# DDR.net
KiCad netlist of a schematic drawn in Altium Designer
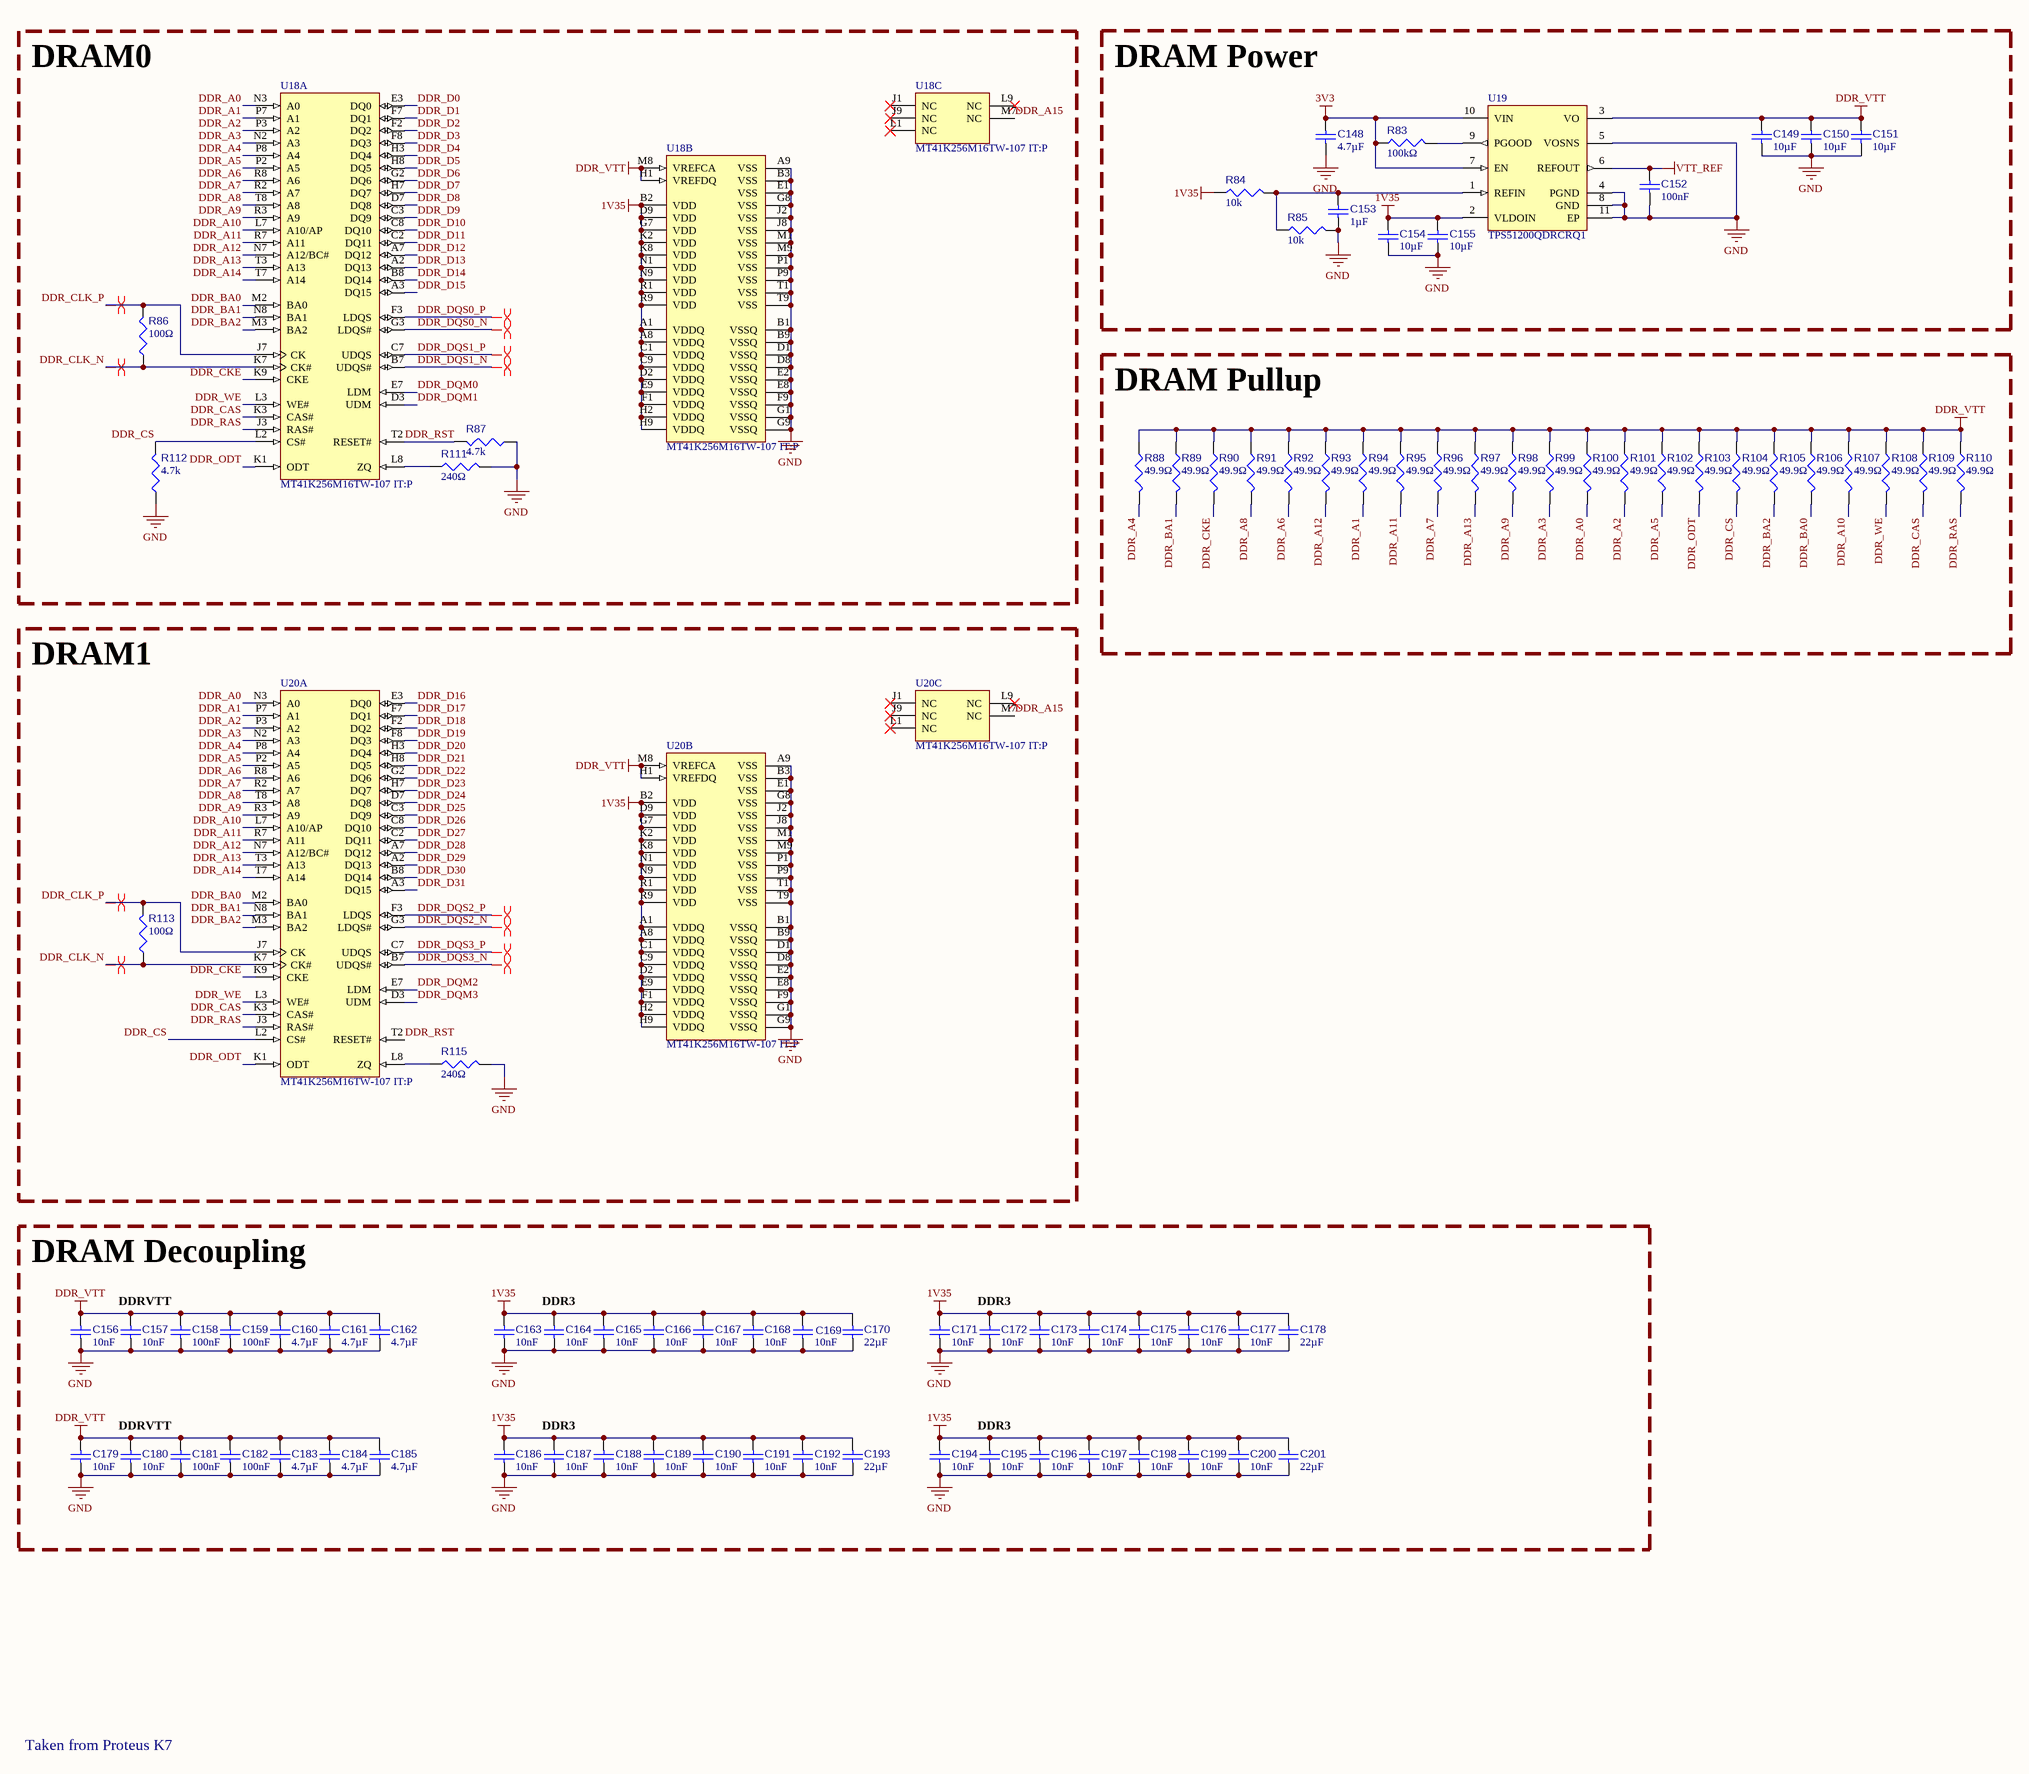
[diagram p0: DDR.SchDoc]

(export (version "E")
  (design (tool "Eeschema 10.0.6"))
  (components
    (comp (ref "C148")
      (value "4.7µF")
      (footprint "CAP-0402-MFG")
      (description "0402-4.7u-20%-25V-X5R")
      (fields (field (name "TOLERANCE") "20%") (field (name "MANUFACTURER PART NUMBER") "GRM155R61E475ME15D"))
      (libsource (lib "UC Berkeley – EE194") (part "CAP-NP-2P"))
    )
    (comp (ref "C149")
      (value "10µF")
      (footprint "CAP-0603-MFG")
      (description "0603-10u-10%-16V-X5R-AECQ200")
      (fields (field (name "TOLERANCE") "10%") (field (name "MANUFACTURER PART NUMBER") "GRT188R61C106KE13J"))
      (libsource (lib "UC Berkeley – EE194") (part "CAP-NP-2P"))
    )
    (comp (ref "C150")
      (value "10µF")
      (footprint "CAP-0603-MFG")
      (description "0603-10u-10%-16V-X5R-AECQ200")
      (fields (field (name "TOLERANCE") "10%") (field (name "MANUFACTURER PART NUMBER") "GRT188R61C106KE13J"))
      (libsource (lib "UC Berkeley – EE194") (part "CAP-NP-2P"))
    )
    (comp (ref "C151")
      (value "10µF")
      (footprint "CAP-0603-MFG")
      (description "0603-10u-10%-16V-X5R-AECQ200")
      (fields (field (name "TOLERANCE") "10%") (field (name "MANUFACTURER PART NUMBER") "GRT188R61C106KE13J"))
      (libsource (lib "UC Berkeley – EE194") (part "CAP-NP-2P"))
    )
    (comp (ref "C152")
      (value "100nF")
      (footprint "CAP-0402-MFG")
      (description "0402-100n-10%-16V-X7R-AECQ200")
      (fields (field (name "TOLERANCE") "10%") (field (name "MANUFACTURER PART NUMBER") "CL05B104KO5VPNC"))
      (libsource (lib "UC Berkeley – EE194") (part "CAP-NP-2P"))
    )
    (comp (ref "C153")
      (value "1µF")
      (footprint "CAP-0402-MFG")
      (description "0402-1u-10%-16V-X6S-AECQ200")
      (fields (field (name "MANUFACTURER PART NUMBER") "GRT155C81C105KE13J") (field (name "TOLERANCE") "10%"))
      (libsource (lib "UC Berkeley – EE194") (part "CAP-NP-2P"))
    )
    (comp (ref "C154")
      (value "10µF")
      (footprint "CAP-0603-MFG")
      (description "0603-10u-10%-16V-X5R-AECQ200")
      (fields (field (name "TOLERANCE") "10%") (field (name "MANUFACTURER PART NUMBER") "GRT188R61C106KE13J"))
      (libsource (lib "UC Berkeley – EE194") (part "CAP-NP-2P"))
    )
    (comp (ref "C155")
      (value "10µF")
      (footprint "CAP-0603-MFG")
      (description "0603-10u-10%-16V-X5R-AECQ200")
      (fields (field (name "TOLERANCE") "10%") (field (name "MANUFACTURER PART NUMBER") "GRT188R61C106KE13J"))
      (libsource (lib "UC Berkeley – EE194") (part "CAP-NP-2P"))
    )
    (comp (ref "C156")
      (value "10nF")
      (footprint "CAP-0402-MFG")
      (description "0402-10n-10%-16V-X7R-AECQ200")
      (fields (field (name "MANUFACTURER PART NUMBER") "AC0402KRX7R7BB103") (field (name "TOLERANCE") "10%"))
      (libsource (lib "UC Berkeley – EE194") (part "CAP-NP-2P"))
    )
    (comp (ref "C157")
      (value "10nF")
      (footprint "CAP-0402-MFG")
      (description "0402-10n-10%-16V-X7R-AECQ200")
      (fields (field (name "MANUFACTURER PART NUMBER") "AC0402KRX7R7BB103") (field (name "TOLERANCE") "10%"))
      (libsource (lib "UC Berkeley – EE194") (part "CAP-NP-2P"))
    )
    (comp (ref "C158")
      (value "100nF")
      (footprint "CAP-0402-MFG")
      (description "0402-100n-10%-16V-X7R-AECQ200")
      (fields (field (name "TOLERANCE") "10%") (field (name "MANUFACTURER PART NUMBER") "CL05B104KO5VPNC"))
      (libsource (lib "UC Berkeley – EE194") (part "CAP-NP-2P"))
    )
    (comp (ref "C159")
      (value "100nF")
      (footprint "CAP-0402-MFG")
      (description "0402-100n-10%-16V-X7R-AECQ200")
      (fields (field (name "TOLERANCE") "10%") (field (name "MANUFACTURER PART NUMBER") "CL05B104KO5VPNC"))
      (libsource (lib "UC Berkeley – EE194") (part "CAP-NP-2P"))
    )
    (comp (ref "C160")
      (value "4.7µF")
      (footprint "CAP-0402-MFG")
      (description "0402-4.7u-20%-25V-X5R")
      (fields (field (name "TOLERANCE") "20%") (field (name "MANUFACTURER PART NUMBER") "GRM155R61E475ME15D"))
      (libsource (lib "UC Berkeley – EE194") (part "CAP-NP-2P"))
    )
    (comp (ref "C161")
      (value "4.7µF")
      (footprint "CAP-0402-MFG")
      (description "0402-4.7u-20%-25V-X5R")
      (fields (field (name "TOLERANCE") "20%") (field (name "MANUFACTURER PART NUMBER") "GRM155R61E475ME15D"))
      (libsource (lib "UC Berkeley – EE194") (part "CAP-NP-2P"))
    )
    (comp (ref "C162")
      (value "4.7µF")
      (footprint "CAP-0402-MFG")
      (description "0402-4.7u-20%-25V-X5R")
      (fields (field (name "TOLERANCE") "20%") (field (name "MANUFACTURER PART NUMBER") "GRM155R61E475ME15D"))
      (libsource (lib "UC Berkeley – EE194") (part "CAP-NP-2P"))
    )
    (comp (ref "C163")
      (value "10nF")
      (footprint "CAP-0402-MFG")
      (description "0402-10n-10%-16V-X7R-AECQ200")
      (fields (field (name "MANUFACTURER PART NUMBER") "AC0402KRX7R7BB103") (field (name "TOLERANCE") "10%"))
      (libsource (lib "UC Berkeley – EE194") (part "CAP-NP-2P"))
    )
    (comp (ref "C164")
      (value "10nF")
      (footprint "CAP-0402-MFG")
      (description "0402-10n-10%-16V-X7R-AECQ200")
      (fields (field (name "MANUFACTURER PART NUMBER") "AC0402KRX7R7BB103") (field (name "TOLERANCE") "10%"))
      (libsource (lib "UC Berkeley – EE194") (part "CAP-NP-2P"))
    )
    (comp (ref "C165")
      (value "10nF")
      (footprint "CAP-0402-MFG")
      (description "0402-10n-10%-16V-X7R-AECQ200")
      (fields (field (name "MANUFACTURER PART NUMBER") "AC0402KRX7R7BB103") (field (name "TOLERANCE") "10%"))
      (libsource (lib "UC Berkeley – EE194") (part "CAP-NP-2P"))
    )
    (comp (ref "C166")
      (value "10nF")
      (footprint "CAP-0402-MFG")
      (description "0402-10n-10%-16V-X7R-AECQ200")
      (fields (field (name "MANUFACTURER PART NUMBER") "AC0402KRX7R7BB103") (field (name "TOLERANCE") "10%"))
      (libsource (lib "UC Berkeley – EE194") (part "CAP-NP-2P"))
    )
    (comp (ref "C167")
      (value "10nF")
      (footprint "CAP-0402-MFG")
      (description "0402-10n-10%-16V-X7R-AECQ200")
      (fields (field (name "MANUFACTURER PART NUMBER") "AC0402KRX7R7BB103") (field (name "TOLERANCE") "10%"))
      (libsource (lib "UC Berkeley – EE194") (part "CAP-NP-2P"))
    )
    (comp (ref "C168")
      (value "10nF")
      (footprint "CAP-0402-MFG")
      (description "0402-10n-10%-16V-X7R-AECQ200")
      (fields (field (name "MANUFACTURER PART NUMBER") "AC0402KRX7R7BB103") (field (name "TOLERANCE") "10%"))
      (libsource (lib "UC Berkeley – EE194") (part "CAP-NP-2P"))
    )
    (comp (ref "C169")
      (value "10nF")
      (footprint "CAP-0402-MFG")
      (description "0402-10n-10%-16V-X7R-AECQ200")
      (fields (field (name "MANUFACTURER PART NUMBER") "AC0402KRX7R7BB103") (field (name "TOLERANCE") "10%"))
      (libsource (lib "UC Berkeley – EE194") (part "CAP-NP-2P"))
    )
    (comp (ref "C170")
      (value "22µF")
      (footprint "CAP-0402-MFG")
      (description "0402-22u-20%-10V-X5R")
      (fields (field (name "TOLERANCE") "20%") (field (name "MANUFACTURER PART NUMBER") "GRM158R61A226ME15D"))
      (libsource (lib "UC Berkeley – EE194") (part "CAP-NP-2P"))
    )
    (comp (ref "C171")
      (value "10nF")
      (footprint "CAP-0402-MFG")
      (description "0402-10n-10%-16V-X7R-AECQ200")
      (fields (field (name "MANUFACTURER PART NUMBER") "AC0402KRX7R7BB103") (field (name "TOLERANCE") "10%"))
      (libsource (lib "UC Berkeley – EE194") (part "CAP-NP-2P"))
    )
    (comp (ref "C172")
      (value "10nF")
      (footprint "CAP-0402-MFG")
      (description "0402-10n-10%-16V-X7R-AECQ200")
      (fields (field (name "MANUFACTURER PART NUMBER") "AC0402KRX7R7BB103") (field (name "TOLERANCE") "10%"))
      (libsource (lib "UC Berkeley – EE194") (part "CAP-NP-2P"))
    )
    (comp (ref "C173")
      (value "10nF")
      (footprint "CAP-0402-MFG")
      (description "0402-10n-10%-16V-X7R-AECQ200")
      (fields (field (name "MANUFACTURER PART NUMBER") "AC0402KRX7R7BB103") (field (name "TOLERANCE") "10%"))
      (libsource (lib "UC Berkeley – EE194") (part "CAP-NP-2P"))
    )
    (comp (ref "C174")
      (value "10nF")
      (footprint "CAP-0402-MFG")
      (description "0402-10n-10%-16V-X7R-AECQ200")
      (fields (field (name "MANUFACTURER PART NUMBER") "AC0402KRX7R7BB103") (field (name "TOLERANCE") "10%"))
      (libsource (lib "UC Berkeley – EE194") (part "CAP-NP-2P"))
    )
    (comp (ref "C175")
      (value "10nF")
      (footprint "CAP-0402-MFG")
      (description "0402-10n-10%-16V-X7R-AECQ200")
      (fields (field (name "MANUFACTURER PART NUMBER") "AC0402KRX7R7BB103") (field (name "TOLERANCE") "10%"))
      (libsource (lib "UC Berkeley – EE194") (part "CAP-NP-2P"))
    )
    (comp (ref "C176")
      (value "10nF")
      (footprint "CAP-0402-MFG")
      (description "0402-10n-10%-16V-X7R-AECQ200")
      (fields (field (name "MANUFACTURER PART NUMBER") "AC0402KRX7R7BB103") (field (name "TOLERANCE") "10%"))
      (libsource (lib "UC Berkeley – EE194") (part "CAP-NP-2P"))
    )
    (comp (ref "C177")
      (value "10nF")
      (footprint "CAP-0402-MFG")
      (description "0402-10n-10%-16V-X7R-AECQ200")
      (fields (field (name "MANUFACTURER PART NUMBER") "AC0402KRX7R7BB103") (field (name "TOLERANCE") "10%"))
      (libsource (lib "UC Berkeley – EE194") (part "CAP-NP-2P"))
    )
    (comp (ref "C178")
      (value "22µF")
      (footprint "CAP-0402-MFG")
      (description "0402-22u-20%-10V-X5R")
      (fields (field (name "TOLERANCE") "20%") (field (name "MANUFACTURER PART NUMBER") "GRM158R61A226ME15D"))
      (libsource (lib "UC Berkeley – EE194") (part "CAP-NP-2P"))
    )
    (comp (ref "C179")
      (value "10nF")
      (footprint "CAP-0402-MFG")
      (description "0402-10n-10%-16V-X7R-AECQ200")
      (fields (field (name "MANUFACTURER PART NUMBER") "AC0402KRX7R7BB103") (field (name "TOLERANCE") "10%"))
      (libsource (lib "UC Berkeley – EE194") (part "CAP-NP-2P"))
    )
    (comp (ref "C180")
      (value "10nF")
      (footprint "CAP-0402-MFG")
      (description "0402-10n-10%-16V-X7R-AECQ200")
      (fields (field (name "MANUFACTURER PART NUMBER") "AC0402KRX7R7BB103") (field (name "TOLERANCE") "10%"))
      (libsource (lib "UC Berkeley – EE194") (part "CAP-NP-2P"))
    )
    (comp (ref "C181")
      (value "100nF")
      (footprint "CAP-0402-MFG")
      (description "0402-100n-10%-16V-X7R-AECQ200")
      (fields (field (name "TOLERANCE") "10%") (field (name "MANUFACTURER PART NUMBER") "CL05B104KO5VPNC"))
      (libsource (lib "UC Berkeley – EE194") (part "CAP-NP-2P"))
    )
    (comp (ref "C182")
      (value "100nF")
      (footprint "CAP-0402-MFG")
      (description "0402-100n-10%-16V-X7R-AECQ200")
      (fields (field (name "TOLERANCE") "10%") (field (name "MANUFACTURER PART NUMBER") "CL05B104KO5VPNC"))
      (libsource (lib "UC Berkeley – EE194") (part "CAP-NP-2P"))
    )
    (comp (ref "C183")
      (value "4.7µF")
      (footprint "CAP-0402-MFG")
      (description "0402-4.7u-20%-25V-X5R")
      (fields (field (name "TOLERANCE") "20%") (field (name "MANUFACTURER PART NUMBER") "GRM155R61E475ME15D"))
      (libsource (lib "UC Berkeley – EE194") (part "CAP-NP-2P"))
    )
    (comp (ref "C184")
      (value "4.7µF")
      (footprint "CAP-0402-MFG")
      (description "0402-4.7u-20%-25V-X5R")
      (fields (field (name "TOLERANCE") "20%") (field (name "MANUFACTURER PART NUMBER") "GRM155R61E475ME15D"))
      (libsource (lib "UC Berkeley – EE194") (part "CAP-NP-2P"))
    )
    (comp (ref "C185")
      (value "4.7µF")
      (footprint "CAP-0402-MFG")
      (description "0402-4.7u-20%-25V-X5R")
      (fields (field (name "TOLERANCE") "20%") (field (name "MANUFACTURER PART NUMBER") "GRM155R61E475ME15D"))
      (libsource (lib "UC Berkeley – EE194") (part "CAP-NP-2P"))
    )
    (comp (ref "C186")
      (value "10nF")
      (footprint "CAP-0402-MFG")
      (description "0402-10n-10%-16V-X7R-AECQ200")
      (fields (field (name "MANUFACTURER PART NUMBER") "AC0402KRX7R7BB103") (field (name "TOLERANCE") "10%"))
      (libsource (lib "UC Berkeley – EE194") (part "CAP-NP-2P"))
    )
    (comp (ref "C187")
      (value "10nF")
      (footprint "CAP-0402-MFG")
      (description "0402-10n-10%-16V-X7R-AECQ200")
      (fields (field (name "MANUFACTURER PART NUMBER") "AC0402KRX7R7BB103") (field (name "TOLERANCE") "10%"))
      (libsource (lib "UC Berkeley – EE194") (part "CAP-NP-2P"))
    )
    (comp (ref "C188")
      (value "10nF")
      (footprint "CAP-0402-MFG")
      (description "0402-10n-10%-16V-X7R-AECQ200")
      (fields (field (name "MANUFACTURER PART NUMBER") "AC0402KRX7R7BB103") (field (name "TOLERANCE") "10%"))
      (libsource (lib "UC Berkeley – EE194") (part "CAP-NP-2P"))
    )
    (comp (ref "C189")
      (value "10nF")
      (footprint "CAP-0402-MFG")
      (description "0402-10n-10%-16V-X7R-AECQ200")
      (fields (field (name "MANUFACTURER PART NUMBER") "AC0402KRX7R7BB103") (field (name "TOLERANCE") "10%"))
      (libsource (lib "UC Berkeley – EE194") (part "CAP-NP-2P"))
    )
    (comp (ref "C190")
      (value "10nF")
      (footprint "CAP-0402-MFG")
      (description "0402-10n-10%-16V-X7R-AECQ200")
      (fields (field (name "MANUFACTURER PART NUMBER") "AC0402KRX7R7BB103") (field (name "TOLERANCE") "10%"))
      (libsource (lib "UC Berkeley – EE194") (part "CAP-NP-2P"))
    )
    (comp (ref "C191")
      (value "10nF")
      (footprint "CAP-0402-MFG")
      (description "0402-10n-10%-16V-X7R-AECQ200")
      (fields (field (name "MANUFACTURER PART NUMBER") "AC0402KRX7R7BB103") (field (name "TOLERANCE") "10%"))
      (libsource (lib "UC Berkeley – EE194") (part "CAP-NP-2P"))
    )
    (comp (ref "C192")
      (value "10nF")
      (footprint "CAP-0402-MFG")
      (description "0402-10n-10%-16V-X7R-AECQ200")
      (fields (field (name "MANUFACTURER PART NUMBER") "AC0402KRX7R7BB103") (field (name "TOLERANCE") "10%"))
      (libsource (lib "UC Berkeley – EE194") (part "CAP-NP-2P"))
    )
    (comp (ref "C193")
      (value "22µF")
      (footprint "CAP-0402-MFG")
      (description "0402-22u-20%-10V-X5R")
      (fields (field (name "TOLERANCE") "20%") (field (name "MANUFACTURER PART NUMBER") "GRM158R61A226ME15D"))
      (libsource (lib "UC Berkeley – EE194") (part "CAP-NP-2P"))
    )
    (comp (ref "C194")
      (value "10nF")
      (footprint "CAP-0402-MFG")
      (description "0402-10n-10%-16V-X7R-AECQ200")
      (fields (field (name "MANUFACTURER PART NUMBER") "AC0402KRX7R7BB103") (field (name "TOLERANCE") "10%"))
      (libsource (lib "UC Berkeley – EE194") (part "CAP-NP-2P"))
    )
    (comp (ref "C195")
      (value "10nF")
      (footprint "CAP-0402-MFG")
      (description "0402-10n-10%-16V-X7R-AECQ200")
      (fields (field (name "MANUFACTURER PART NUMBER") "AC0402KRX7R7BB103") (field (name "TOLERANCE") "10%"))
      (libsource (lib "UC Berkeley – EE194") (part "CAP-NP-2P"))
    )
    (comp (ref "C196")
      (value "10nF")
      (footprint "CAP-0402-MFG")
      (description "0402-10n-10%-16V-X7R-AECQ200")
      (fields (field (name "MANUFACTURER PART NUMBER") "AC0402KRX7R7BB103") (field (name "TOLERANCE") "10%"))
      (libsource (lib "UC Berkeley – EE194") (part "CAP-NP-2P"))
    )
    (comp (ref "C197")
      (value "10nF")
      (footprint "CAP-0402-MFG")
      (description "0402-10n-10%-16V-X7R-AECQ200")
      (fields (field (name "MANUFACTURER PART NUMBER") "AC0402KRX7R7BB103") (field (name "TOLERANCE") "10%"))
      (libsource (lib "UC Berkeley – EE194") (part "CAP-NP-2P"))
    )
    (comp (ref "C198")
      (value "10nF")
      (footprint "CAP-0402-MFG")
      (description "0402-10n-10%-16V-X7R-AECQ200")
      (fields (field (name "MANUFACTURER PART NUMBER") "AC0402KRX7R7BB103") (field (name "TOLERANCE") "10%"))
      (libsource (lib "UC Berkeley – EE194") (part "CAP-NP-2P"))
    )
    (comp (ref "C199")
      (value "10nF")
      (footprint "CAP-0402-MFG")
      (description "0402-10n-10%-16V-X7R-AECQ200")
      (fields (field (name "MANUFACTURER PART NUMBER") "AC0402KRX7R7BB103") (field (name "TOLERANCE") "10%"))
      (libsource (lib "UC Berkeley – EE194") (part "CAP-NP-2P"))
    )
    (comp (ref "C200")
      (value "10nF")
      (footprint "CAP-0402-MFG")
      (description "0402-10n-10%-16V-X7R-AECQ200")
      (fields (field (name "MANUFACTURER PART NUMBER") "AC0402KRX7R7BB103") (field (name "TOLERANCE") "10%"))
      (libsource (lib "UC Berkeley – EE194") (part "CAP-NP-2P"))
    )
    (comp (ref "C201")
      (value "22µF")
      (footprint "CAP-0402-MFG")
      (description "0402-22u-20%-10V-X5R")
      (fields (field (name "TOLERANCE") "20%") (field (name "MANUFACTURER PART NUMBER") "GRM158R61A226ME15D"))
      (libsource (lib "UC Berkeley – EE194") (part "CAP-NP-2P"))
    )
    (comp (ref "R83")
      (value "100kΩ")
      (footprint "RES-0402")
      (description "0402-100k-1%-1/16W-AEC-Q200")
      (fields (field (name "MANUFACTURER PART NUMBER") "AC0402FR-07100KL") (field (name "TOLERANCE") "1%"))
      (libsource (lib "UC Berkeley – EE194") (part "RES-2P"))
    )
    (comp (ref "R84")
      (value "10k")
      (footprint "RES-0402")
      (description "0402-10k-1%-1/16W-AEC-Q200")
      (fields (field (name "TOLERANCE") "1%") (field (name "MANUFACTURER PART NUMBER") "AC0402FR-0710KL"))
      (libsource (lib "UC Berkeley – EE194") (part "RES-2P"))
    )
    (comp (ref "R85")
      (value "10k")
      (footprint "RES-0402")
      (description "0402-10k-1%-1/16W-AEC-Q200")
      (fields (field (name "TOLERANCE") "1%") (field (name "MANUFACTURER PART NUMBER") "AC0402FR-0710KL"))
      (libsource (lib "UC Berkeley – EE194") (part "RES-2P"))
    )
    (comp (ref "R86")
      (value "100Ω")
      (footprint "RES-0402")
      (description "0402-100-1%-1/16W-AEC-Q200")
      (fields (field (name "MANUFACTURER PART NUMBER") "AC0402FR-07100RL") (field (name "POWER") "63mW"))
      (libsource (lib "UC Berkeley – EE194") (part "RES-2P"))
    )
    (comp (ref "R87")
      (value "4.7k")
      (footprint "RES-0402")
      (description "0402-4.7k-1%-1/16W-AEC-Q200")
      (fields (field (name "TOLERANCE") "1%") (field (name "POWER") "63mW"))
      (libsource (lib "UC Berkeley – EE194") (part "RES-2P"))
    )
    (comp (ref "R88")
      (value "49.9Ω")
      (footprint "RES-0402")
      (description "0402-49.9-1%-1/16W-AEC-Q200")
      (fields (field (name "MANUFACTURER PART NUMBER") "CRCW040249R9FKED") (field (name "TOLERANCE") "1%"))
      (libsource (lib "UC Berkeley – EE194") (part "RES-2P"))
    )
    (comp (ref "R89")
      (value "49.9Ω")
      (footprint "RES-0402")
      (description "0402-49.9-1%-1/16W-AEC-Q200")
      (fields (field (name "MANUFACTURER PART NUMBER") "CRCW040249R9FKED") (field (name "TOLERANCE") "1%"))
      (libsource (lib "UC Berkeley – EE194") (part "RES-2P"))
    )
    (comp (ref "R90")
      (value "49.9Ω")
      (footprint "RES-0402")
      (description "0402-49.9-1%-1/16W-AEC-Q200")
      (fields (field (name "MANUFACTURER PART NUMBER") "CRCW040249R9FKED") (field (name "TOLERANCE") "1%"))
      (libsource (lib "UC Berkeley – EE194") (part "RES-2P"))
    )
    (comp (ref "R91")
      (value "49.9Ω")
      (footprint "RES-0402")
      (description "0402-49.9-1%-1/16W-AEC-Q200")
      (fields (field (name "MANUFACTURER PART NUMBER") "CRCW040249R9FKED") (field (name "TOLERANCE") "1%"))
      (libsource (lib "UC Berkeley – EE194") (part "RES-2P"))
    )
    (comp (ref "R92")
      (value "49.9Ω")
      (footprint "RES-0402")
      (description "0402-49.9-1%-1/16W-AEC-Q200")
      (fields (field (name "MANUFACTURER PART NUMBER") "CRCW040249R9FKED") (field (name "TOLERANCE") "1%"))
      (libsource (lib "UC Berkeley – EE194") (part "RES-2P"))
    )
    (comp (ref "R93")
      (value "49.9Ω")
      (footprint "RES-0402")
      (description "0402-49.9-1%-1/16W-AEC-Q200")
      (fields (field (name "MANUFACTURER PART NUMBER") "CRCW040249R9FKED") (field (name "TOLERANCE") "1%"))
      (libsource (lib "UC Berkeley – EE194") (part "RES-2P"))
    )
    (comp (ref "R94")
      (value "49.9Ω")
      (footprint "RES-0402")
      (description "0402-49.9-1%-1/16W-AEC-Q200")
      (fields (field (name "MANUFACTURER PART NUMBER") "CRCW040249R9FKED") (field (name "TOLERANCE") "1%"))
      (libsource (lib "UC Berkeley – EE194") (part "RES-2P"))
    )
    (comp (ref "R95")
      (value "49.9Ω")
      (footprint "RES-0402")
      (description "0402-49.9-1%-1/16W-AEC-Q200")
      (fields (field (name "MANUFACTURER PART NUMBER") "CRCW040249R9FKED") (field (name "TOLERANCE") "1%"))
      (libsource (lib "UC Berkeley – EE194") (part "RES-2P"))
    )
    (comp (ref "R96")
      (value "49.9Ω")
      (footprint "RES-0402")
      (description "0402-49.9-1%-1/16W-AEC-Q200")
      (fields (field (name "MANUFACTURER PART NUMBER") "CRCW040249R9FKED") (field (name "TOLERANCE") "1%"))
      (libsource (lib "UC Berkeley – EE194") (part "RES-2P"))
    )
    (comp (ref "R97")
      (value "49.9Ω")
      (footprint "RES-0402")
      (description "0402-49.9-1%-1/16W-AEC-Q200")
      (fields (field (name "MANUFACTURER PART NUMBER") "CRCW040249R9FKED") (field (name "TOLERANCE") "1%"))
      (libsource (lib "UC Berkeley – EE194") (part "RES-2P"))
    )
    (comp (ref "R98")
      (value "49.9Ω")
      (footprint "RES-0402")
      (description "0402-49.9-1%-1/16W-AEC-Q200")
      (fields (field (name "MANUFACTURER PART NUMBER") "CRCW040249R9FKED") (field (name "TOLERANCE") "1%"))
      (libsource (lib "UC Berkeley – EE194") (part "RES-2P"))
    )
    (comp (ref "R99")
      (value "49.9Ω")
      (footprint "RES-0402")
      (description "0402-49.9-1%-1/16W-AEC-Q200")
      (fields (field (name "MANUFACTURER PART NUMBER") "CRCW040249R9FKED") (field (name "TOLERANCE") "1%"))
      (libsource (lib "UC Berkeley – EE194") (part "RES-2P"))
    )
    (comp (ref "R100")
      (value "49.9Ω")
      (footprint "RES-0402")
      (description "0402-49.9-1%-1/16W-AEC-Q200")
      (fields (field (name "MANUFACTURER PART NUMBER") "CRCW040249R9FKED") (field (name "TOLERANCE") "1%"))
      (libsource (lib "UC Berkeley – EE194") (part "RES-2P"))
    )
    (comp (ref "R101")
      (value "49.9Ω")
      (footprint "RES-0402")
      (description "0402-49.9-1%-1/16W-AEC-Q200")
      (fields (field (name "MANUFACTURER PART NUMBER") "CRCW040249R9FKED") (field (name "TOLERANCE") "1%"))
      (libsource (lib "UC Berkeley – EE194") (part "RES-2P"))
    )
    (comp (ref "R102")
      (value "49.9Ω")
      (footprint "RES-0402")
      (description "0402-49.9-1%-1/16W-AEC-Q200")
      (fields (field (name "MANUFACTURER PART NUMBER") "CRCW040249R9FKED") (field (name "TOLERANCE") "1%"))
      (libsource (lib "UC Berkeley – EE194") (part "RES-2P"))
    )
    (comp (ref "R103")
      (value "49.9Ω")
      (footprint "RES-0402")
      (description "0402-49.9-1%-1/16W-AEC-Q200")
      (fields (field (name "MANUFACTURER PART NUMBER") "CRCW040249R9FKED") (field (name "TOLERANCE") "1%"))
      (libsource (lib "UC Berkeley – EE194") (part "RES-2P"))
    )
    (comp (ref "R104")
      (value "49.9Ω")
      (footprint "RES-0402")
      (description "0402-49.9-1%-1/16W-AEC-Q200")
      (fields (field (name "MANUFACTURER PART NUMBER") "CRCW040249R9FKED") (field (name "TOLERANCE") "1%"))
      (libsource (lib "UC Berkeley – EE194") (part "RES-2P"))
    )
    (comp (ref "R105")
      (value "49.9Ω")
      (footprint "RES-0402")
      (description "0402-49.9-1%-1/16W-AEC-Q200")
      (fields (field (name "MANUFACTURER PART NUMBER") "CRCW040249R9FKED") (field (name "TOLERANCE") "1%"))
      (libsource (lib "UC Berkeley – EE194") (part "RES-2P"))
    )
    (comp (ref "R106")
      (value "49.9Ω")
      (footprint "RES-0402")
      (description "0402-49.9-1%-1/16W-AEC-Q200")
      (fields (field (name "MANUFACTURER PART NUMBER") "CRCW040249R9FKED") (field (name "TOLERANCE") "1%"))
      (libsource (lib "UC Berkeley – EE194") (part "RES-2P"))
    )
    (comp (ref "R107")
      (value "49.9Ω")
      (footprint "RES-0402")
      (description "0402-49.9-1%-1/16W-AEC-Q200")
      (fields (field (name "MANUFACTURER PART NUMBER") "CRCW040249R9FKED") (field (name "TOLERANCE") "1%"))
      (libsource (lib "UC Berkeley – EE194") (part "RES-2P"))
    )
    (comp (ref "R108")
      (value "49.9Ω")
      (footprint "RES-0402")
      (description "0402-49.9-1%-1/16W-AEC-Q200")
      (fields (field (name "MANUFACTURER PART NUMBER") "CRCW040249R9FKED") (field (name "TOLERANCE") "1%"))
      (libsource (lib "UC Berkeley – EE194") (part "RES-2P"))
    )
    (comp (ref "R109")
      (value "49.9Ω")
      (footprint "RES-0402")
      (description "0402-49.9-1%-1/16W-AEC-Q200")
      (fields (field (name "MANUFACTURER PART NUMBER") "CRCW040249R9FKED") (field (name "TOLERANCE") "1%"))
      (libsource (lib "UC Berkeley – EE194") (part "RES-2P"))
    )
    (comp (ref "R110")
      (value "49.9Ω")
      (footprint "RES-0402")
      (description "0402-49.9-1%-1/16W-AEC-Q200")
      (fields (field (name "MANUFACTURER PART NUMBER") "CRCW040249R9FKED") (field (name "TOLERANCE") "1%"))
      (libsource (lib "UC Berkeley – EE194") (part "RES-2P"))
    )
    (comp (ref "R111")
      (value "240Ω")
      (footprint "RES-0402")
      (description "0402-240-1%-1/16W-AEC-Q200")
      (fields (field (name "POWER") "63mW") (field (name "MANUFACTURER PART NUMBER") "AC0402FR-07240RL"))
      (libsource (lib "UC Berkeley – EE194") (part "RES-2P"))
    )
    (comp (ref "R112")
      (value "4.7k")
      (footprint "RES-0402")
      (description "0402-4.7k-1%-1/16W-AEC-Q200")
      (fields (field (name "TOLERANCE") "1%") (field (name "POWER") "63mW"))
      (libsource (lib "UC Berkeley – EE194") (part "RES-2P"))
    )
    (comp (ref "R113")
      (value "100Ω")
      (footprint "RES-0402")
      (description "0402-100-1%-1/16W-AEC-Q200")
      (fields (field (name "MANUFACTURER PART NUMBER") "AC0402FR-07100RL") (field (name "POWER") "63mW"))
      (libsource (lib "UC Berkeley – EE194") (part "RES-2P"))
    )
    (comp (ref "R115")
      (value "240Ω")
      (footprint "RES-0402")
      (description "0402-240-1%-1/16W-AEC-Q200")
      (fields (field (name "POWER") "63mW") (field (name "MANUFACTURER PART NUMBER") "AC0402FR-07240RL"))
      (libsource (lib "UC Berkeley – EE194") (part "RES-2P"))
    )
    (comp (ref "U18")
      (value "MT41K256M16TW-107 IT:P")
      (footprint "MICT-TW-96")
      (description "IC DRAM 4GBIT PAR 96FBGA SDRAM - DDR3L Memory IC 4Gbit Parallel 933 MHz 20 ns 96-FBGA (8x14)")
      (libsource (lib "UC Berkeley – EE194") (part "MICT-MT41K256M16-TW-96"))
    )
    (comp (ref "U19")
      (value "TPS51200QDRCRQ1")
      (footprint "FP-DRC0010J-MFG")
      (description "DDR/DDR2/DDR3/DDR3L/LPDDR3/DDR4 Termination Regulator 3A 2.375V to 3.5V 10-Pin VSON T/R")
      (libsource (lib "UC Berkeley – EE194") (part "TPS51200QDRCRQ1"))
    )
    (comp (ref "U20")
      (value "MT41K256M16TW-107 IT:P")
      (footprint "MICT-TW-96")
      (description "IC DRAM 4GBIT PAR 96FBGA SDRAM - DDR3L Memory IC 4Gbit Parallel 933 MHz 20 ns 96-FBGA (8x14)")
      (libsource (lib "UC Berkeley – EE194") (part "MICT-MT41K256M16-TW-96"))
    )
  )
  (nets
    (net (code "1") (name "/DDR_A0") (class "Default")
      (node (ref "R100") (pin "2") (pinfunction "2_2") (pintype "passive"))
      (node (ref "U18") (pin "N3") (pinfunction "A0_N3") (pintype "input"))
      (node (ref "U20") (pin "N3") (pinfunction "A0_N3") (pintype "input"))
    )
    (net (code "2") (name "/DDR_A1") (class "Default")
      (node (ref "R94") (pin "2") (pinfunction "2_2") (pintype "passive"))
      (node (ref "U18") (pin "P7") (pinfunction "A1_P7") (pintype "input"))
      (node (ref "U20") (pin "P7") (pinfunction "A1_P7") (pintype "input"))
    )
    (net (code "3") (name "/DDR_A2") (class "Default")
      (node (ref "R101") (pin "2") (pinfunction "2_2") (pintype "passive"))
      (node (ref "U18") (pin "P3") (pinfunction "A2_P3") (pintype "input"))
      (node (ref "U20") (pin "P3") (pinfunction "A2_P3") (pintype "input"))
    )
    (net (code "4") (name "/DDR_A3") (class "Default")
      (node (ref "R99") (pin "2") (pinfunction "2_2") (pintype "passive"))
      (node (ref "U18") (pin "N2") (pinfunction "A3_N2") (pintype "input"))
      (node (ref "U20") (pin "N2") (pinfunction "A3_N2") (pintype "input"))
    )
    (net (code "5") (name "/DDR_A4") (class "Default")
      (node (ref "R88") (pin "2") (pinfunction "2_2") (pintype "passive"))
      (node (ref "U18") (pin "P8") (pinfunction "A4_P8") (pintype "input"))
      (node (ref "U20") (pin "P8") (pinfunction "A4_P8") (pintype "input"))
    )
    (net (code "6") (name "/DDR_A5") (class "Default")
      (node (ref "R102") (pin "2") (pinfunction "2_2") (pintype "passive"))
      (node (ref "U18") (pin "P2") (pinfunction "A5_P2") (pintype "input"))
      (node (ref "U20") (pin "P2") (pinfunction "A5_P2") (pintype "input"))
    )
    (net (code "7") (name "/DDR_A6") (class "Default")
      (node (ref "R92") (pin "2") (pinfunction "2_2") (pintype "passive"))
      (node (ref "U18") (pin "R8") (pinfunction "A6_R8") (pintype "input"))
      (node (ref "U20") (pin "R8") (pinfunction "A6_R8") (pintype "input"))
    )
    (net (code "8") (name "/DDR_A7") (class "Default")
      (node (ref "R96") (pin "2") (pinfunction "2_2") (pintype "passive"))
      (node (ref "U18") (pin "R2") (pinfunction "A7_R2") (pintype "input"))
      (node (ref "U20") (pin "R2") (pinfunction "A7_R2") (pintype "input"))
    )
    (net (code "9") (name "/DDR_A8") (class "Default")
      (node (ref "R91") (pin "2") (pinfunction "2_2") (pintype "passive"))
      (node (ref "U18") (pin "T8") (pinfunction "A8_T8") (pintype "input"))
      (node (ref "U20") (pin "T8") (pinfunction "A8_T8") (pintype "input"))
    )
    (net (code "10") (name "/DDR_A9") (class "Default")
      (node (ref "R98") (pin "2") (pinfunction "2_2") (pintype "passive"))
      (node (ref "U18") (pin "R3") (pinfunction "A9_R3") (pintype "input"))
      (node (ref "U20") (pin "R3") (pinfunction "A9_R3") (pintype "input"))
    )
    (net (code "11") (name "/DDR_A10") (class "Default")
      (node (ref "R107") (pin "2") (pinfunction "2_2") (pintype "passive"))
      (node (ref "U18") (pin "L7") (pinfunction "A10/AP_L7") (pintype "input"))
      (node (ref "U20") (pin "L7") (pinfunction "A10/AP_L7") (pintype "input"))
    )
    (net (code "12") (name "/DDR_A11") (class "Default")
      (node (ref "R95") (pin "2") (pinfunction "2_2") (pintype "passive"))
      (node (ref "U18") (pin "R7") (pinfunction "A11_R7") (pintype "input"))
      (node (ref "U20") (pin "R7") (pinfunction "A11_R7") (pintype "input"))
    )
    (net (code "13") (name "/DDR_A12") (class "Default")
      (node (ref "R93") (pin "2") (pinfunction "2_2") (pintype "passive"))
      (node (ref "U18") (pin "N7") (pinfunction "A12/BC#_N7") (pintype "input"))
      (node (ref "U20") (pin "N7") (pinfunction "A12/BC#_N7") (pintype "input"))
    )
    (net (code "14") (name "/DDR_A13") (class "Default")
      (node (ref "R97") (pin "2") (pinfunction "2_2") (pintype "passive"))
      (node (ref "U18") (pin "T3") (pinfunction "A13_T3") (pintype "input"))
      (node (ref "U20") (pin "T3") (pinfunction "A13_T3") (pintype "input"))
    )
    (net (code "15") (name "/DDR_A14") (class "Default")
      (node (ref "U18") (pin "T7") (pinfunction "A14_T7") (pintype "input"))
      (node (ref "U20") (pin "T7") (pinfunction "A14_T7") (pintype "input"))
    )
    (net (code "16") (name "/DDR_A15") (class "Default")
      (node (ref "U18") (pin "M7") (pinfunction "NC_M7") (pintype "passive"))
      (node (ref "U20") (pin "M7") (pinfunction "NC_M7") (pintype "passive"))
    )
    (net (code "17") (name "/DDR_BA0") (class "Default")
      (node (ref "R106") (pin "2") (pinfunction "2_2") (pintype "passive"))
      (node (ref "U18") (pin "M2") (pinfunction "BA0_M2") (pintype "input"))
      (node (ref "U20") (pin "M2") (pinfunction "BA0_M2") (pintype "input"))
    )
    (net (code "18") (name "/DDR_BA1") (class "Default")
      (node (ref "R89") (pin "2") (pinfunction "2_2") (pintype "passive"))
      (node (ref "U18") (pin "N8") (pinfunction "BA1_N8") (pintype "input"))
      (node (ref "U20") (pin "N8") (pinfunction "BA1_N8") (pintype "input"))
    )
    (net (code "19") (name "/DDR_BA2") (class "Default")
      (node (ref "R105") (pin "2") (pinfunction "2_2") (pintype "passive"))
      (node (ref "U18") (pin "M3") (pinfunction "BA2_M3") (pintype "input"))
      (node (ref "U20") (pin "M3") (pinfunction "BA2_M3") (pintype "input"))
    )
    (net (code "20") (name "/DDR_CAS") (class "Default")
      (node (ref "R109") (pin "2") (pinfunction "2_2") (pintype "passive"))
      (node (ref "U18") (pin "K3") (pinfunction "CAS#_K3") (pintype "input"))
      (node (ref "U20") (pin "K3") (pinfunction "CAS#_K3") (pintype "input"))
    )
    (net (code "21") (name "/DDR_CKE") (class "Default")
      (node (ref "R90") (pin "2") (pinfunction "2_2") (pintype "passive"))
      (node (ref "U18") (pin "K9") (pinfunction "CKE_K9") (pintype "input"))
      (node (ref "U20") (pin "K9") (pinfunction "CKE_K9") (pintype "input"))
    )
    (net (code "22") (name "/DDR_CLK_N") (class "Default")
      (node (ref "R113") (pin "1") (pinfunction "1_1") (pintype "passive"))
      (node (ref "R86") (pin "1") (pinfunction "1_1") (pintype "passive"))
      (node (ref "U18") (pin "K7") (pinfunction "CK#_K7") (pintype "input"))
      (node (ref "U20") (pin "K7") (pinfunction "CK#_K7") (pintype "input"))
    )
    (net (code "23") (name "/DDR_CLK_P") (class "Default")
      (node (ref "R113") (pin "2") (pinfunction "2_2") (pintype "passive"))
      (node (ref "R86") (pin "2") (pinfunction "2_2") (pintype "passive"))
      (node (ref "U18") (pin "J7") (pinfunction "CK_J7") (pintype "input"))
      (node (ref "U20") (pin "J7") (pinfunction "CK_J7") (pintype "input"))
    )
    (net (code "24") (name "/DDR_CS") (class "Default")
      (node (ref "R104") (pin "2") (pinfunction "2_2") (pintype "passive"))
      (node (ref "R112") (pin "2") (pinfunction "2_2") (pintype "passive"))
      (node (ref "U18") (pin "L2") (pinfunction "CS#_L2") (pintype "input"))
      (node (ref "U20") (pin "L2") (pinfunction "CS#_L2") (pintype "input"))
    )
    (net (code "25") (name "/DDR_D0") (class "Default")
      (node (ref "U18") (pin "E3") (pinfunction "DQ0_E3") (pintype "bidirectional"))
    )
    (net (code "26") (name "/DDR_D1") (class "Default")
      (node (ref "U18") (pin "F7") (pinfunction "DQ1_F7") (pintype "bidirectional"))
    )
    (net (code "27") (name "/DDR_D2") (class "Default")
      (node (ref "U18") (pin "F2") (pinfunction "DQ2_F2") (pintype "bidirectional"))
    )
    (net (code "28") (name "/DDR_D3") (class "Default")
      (node (ref "U18") (pin "F8") (pinfunction "DQ3_F8") (pintype "bidirectional"))
    )
    (net (code "29") (name "/DDR_D4") (class "Default")
      (node (ref "U18") (pin "H3") (pinfunction "DQ4_H3") (pintype "bidirectional"))
    )
    (net (code "30") (name "/DDR_D5") (class "Default")
      (node (ref "U18") (pin "H8") (pinfunction "DQ5_H8") (pintype "bidirectional"))
    )
    (net (code "31") (name "/DDR_D6") (class "Default")
      (node (ref "U18") (pin "G2") (pinfunction "DQ6_G2") (pintype "bidirectional"))
    )
    (net (code "32") (name "/DDR_D7") (class "Default")
      (node (ref "U18") (pin "H7") (pinfunction "DQ7_H7") (pintype "bidirectional"))
    )
    (net (code "33") (name "/DDR_D8") (class "Default")
      (node (ref "U18") (pin "D7") (pinfunction "DQ8_D7") (pintype "bidirectional"))
    )
    (net (code "34") (name "/DDR_D9") (class "Default")
      (node (ref "U18") (pin "C3") (pinfunction "DQ9_C3") (pintype "bidirectional"))
    )
    (net (code "35") (name "/DDR_D10") (class "Default")
      (node (ref "U18") (pin "C8") (pinfunction "DQ10_C8") (pintype "bidirectional"))
    )
    (net (code "36") (name "/DDR_D11") (class "Default")
      (node (ref "U18") (pin "C2") (pinfunction "DQ11_C2") (pintype "bidirectional"))
    )
    (net (code "37") (name "/DDR_D12") (class "Default")
      (node (ref "U18") (pin "A7") (pinfunction "DQ12_A7") (pintype "bidirectional"))
    )
    (net (code "38") (name "/DDR_D13") (class "Default")
      (node (ref "U18") (pin "A2") (pinfunction "DQ13_A2") (pintype "bidirectional"))
    )
    (net (code "39") (name "/DDR_D14") (class "Default")
      (node (ref "U18") (pin "B8") (pinfunction "DQ14_B8") (pintype "bidirectional"))
    )
    (net (code "40") (name "/DDR_D15") (class "Default")
      (node (ref "U18") (pin "A3") (pinfunction "DQ15_A3") (pintype "bidirectional"))
    )
    (net (code "41") (name "/DDR_D16") (class "Default")
      (node (ref "U20") (pin "E3") (pinfunction "DQ0_E3") (pintype "bidirectional"))
    )
    (net (code "42") (name "/DDR_D17") (class "Default")
      (node (ref "U20") (pin "F7") (pinfunction "DQ1_F7") (pintype "bidirectional"))
    )
    (net (code "43") (name "/DDR_D18") (class "Default")
      (node (ref "U20") (pin "F2") (pinfunction "DQ2_F2") (pintype "bidirectional"))
    )
    (net (code "44") (name "/DDR_D19") (class "Default")
      (node (ref "U20") (pin "F8") (pinfunction "DQ3_F8") (pintype "bidirectional"))
    )
    (net (code "45") (name "/DDR_D20") (class "Default")
      (node (ref "U20") (pin "H3") (pinfunction "DQ4_H3") (pintype "bidirectional"))
    )
    (net (code "46") (name "/DDR_D21") (class "Default")
      (node (ref "U20") (pin "H8") (pinfunction "DQ5_H8") (pintype "bidirectional"))
    )
    (net (code "47") (name "/DDR_D22") (class "Default")
      (node (ref "U20") (pin "G2") (pinfunction "DQ6_G2") (pintype "bidirectional"))
    )
    (net (code "48") (name "/DDR_D23") (class "Default")
      (node (ref "U20") (pin "H7") (pinfunction "DQ7_H7") (pintype "bidirectional"))
    )
    (net (code "49") (name "/DDR_D24") (class "Default")
      (node (ref "U20") (pin "D7") (pinfunction "DQ8_D7") (pintype "bidirectional"))
    )
    (net (code "50") (name "/DDR_D25") (class "Default")
      (node (ref "U20") (pin "C3") (pinfunction "DQ9_C3") (pintype "bidirectional"))
    )
    (net (code "51") (name "/DDR_D26") (class "Default")
      (node (ref "U20") (pin "C8") (pinfunction "DQ10_C8") (pintype "bidirectional"))
    )
    (net (code "52") (name "/DDR_D27") (class "Default")
      (node (ref "U20") (pin "C2") (pinfunction "DQ11_C2") (pintype "bidirectional"))
    )
    (net (code "53") (name "/DDR_D28") (class "Default")
      (node (ref "U20") (pin "A7") (pinfunction "DQ12_A7") (pintype "bidirectional"))
    )
    (net (code "54") (name "/DDR_D29") (class "Default")
      (node (ref "U20") (pin "A2") (pinfunction "DQ13_A2") (pintype "bidirectional"))
    )
    (net (code "55") (name "/DDR_D30") (class "Default")
      (node (ref "U20") (pin "B8") (pinfunction "DQ14_B8") (pintype "bidirectional"))
    )
    (net (code "56") (name "/DDR_D31") (class "Default")
      (node (ref "U20") (pin "A3") (pinfunction "DQ15_A3") (pintype "bidirectional"))
    )
    (net (code "57") (name "/DDR_DQM0") (class "Default")
      (node (ref "U18") (pin "E7") (pinfunction "LDM_E7") (pintype "input"))
    )
    (net (code "58") (name "/DDR_DQM1") (class "Default")
      (node (ref "U18") (pin "D3") (pinfunction "UDM_D3") (pintype "input"))
    )
    (net (code "59") (name "/DDR_DQM2") (class "Default")
      (node (ref "U20") (pin "E7") (pinfunction "LDM_E7") (pintype "input"))
    )
    (net (code "60") (name "/DDR_DQM3") (class "Default")
      (node (ref "U20") (pin "D3") (pinfunction "UDM_D3") (pintype "input"))
    )
    (net (code "61") (name "/DDR_DQS0_N") (class "Default")
      (node (ref "U18") (pin "G3") (pinfunction "LDQS#_G3") (pintype "bidirectional"))
    )
    (net (code "62") (name "/DDR_DQS0_P") (class "Default")
      (node (ref "U18") (pin "F3") (pinfunction "LDQS_F3") (pintype "bidirectional"))
    )
    (net (code "63") (name "/DDR_DQS1_N") (class "Default")
      (node (ref "U18") (pin "B7") (pinfunction "UDQS#_B7") (pintype "bidirectional"))
    )
    (net (code "64") (name "/DDR_DQS1_P") (class "Default")
      (node (ref "U18") (pin "C7") (pinfunction "UDQS_C7") (pintype "bidirectional"))
    )
    (net (code "65") (name "/DDR_DQS2_N") (class "Default")
      (node (ref "U20") (pin "G3") (pinfunction "LDQS#_G3") (pintype "bidirectional"))
    )
    (net (code "66") (name "/DDR_DQS2_P") (class "Default")
      (node (ref "U20") (pin "F3") (pinfunction "LDQS_F3") (pintype "bidirectional"))
    )
    (net (code "67") (name "/DDR_DQS3_N") (class "Default")
      (node (ref "U20") (pin "B7") (pinfunction "UDQS#_B7") (pintype "bidirectional"))
    )
    (net (code "68") (name "/DDR_DQS3_P") (class "Default")
      (node (ref "U20") (pin "C7") (pinfunction "UDQS_C7") (pintype "bidirectional"))
    )
    (net (code "69") (name "/DDR_ODT") (class "Default")
      (node (ref "R103") (pin "2") (pinfunction "2_2") (pintype "passive"))
      (node (ref "U18") (pin "K1") (pinfunction "ODT_K1") (pintype "input"))
      (node (ref "U20") (pin "K1") (pinfunction "ODT_K1") (pintype "input"))
    )
    (net (code "70") (name "/DDR_RAS") (class "Default")
      (node (ref "R110") (pin "2") (pinfunction "2_2") (pintype "passive"))
      (node (ref "U18") (pin "J3") (pinfunction "RAS#_J3") (pintype "input"))
      (node (ref "U20") (pin "J3") (pinfunction "RAS#_J3") (pintype "input"))
    )
    (net (code "71") (name "/DDR_RST") (class "Default")
      (node (ref "R87") (pin "2") (pinfunction "2_2") (pintype "passive"))
      (node (ref "U18") (pin "T2") (pinfunction "RESET#_T2") (pintype "input"))
      (node (ref "U20") (pin "T2") (pinfunction "RESET#_T2") (pintype "input"))
    )
    (net (code "72") (name "/DDR_WE") (class "Default")
      (node (ref "R108") (pin "2") (pinfunction "2_2") (pintype "passive"))
      (node (ref "U18") (pin "L3") (pinfunction "WE#_L3") (pintype "input"))
      (node (ref "U20") (pin "L3") (pinfunction "WE#_L3") (pintype "input"))
    )
    (net (code "73") (name "1V35") (class "Default")
      (node (ref "C154") (pin "1") (pinfunction "1_1") (pintype "passive"))
      (node (ref "C155") (pin "1") (pinfunction "1_1") (pintype "passive"))
      (node (ref "C163") (pin "1") (pinfunction "1_1") (pintype "passive"))
      (node (ref "C164") (pin "1") (pinfunction "1_1") (pintype "passive"))
      (node (ref "C165") (pin "1") (pinfunction "1_1") (pintype "passive"))
      (node (ref "C166") (pin "1") (pinfunction "1_1") (pintype "passive"))
      (node (ref "C167") (pin "1") (pinfunction "1_1") (pintype "passive"))
      (node (ref "C168") (pin "2") (pinfunction "2_2") (pintype "passive"))
      (node (ref "C169") (pin "1") (pinfunction "1_1") (pintype "passive"))
      (node (ref "C170") (pin "1") (pinfunction "1_1") (pintype "passive"))
      (node (ref "C171") (pin "1") (pinfunction "1_1") (pintype "passive"))
      (node (ref "C172") (pin "2") (pinfunction "2_2") (pintype "passive"))
      (node (ref "C173") (pin "2") (pinfunction "2_2") (pintype "passive"))
      (node (ref "C174") (pin "2") (pinfunction "2_2") (pintype "passive"))
      (node (ref "C175") (pin "2") (pinfunction "2_2") (pintype "passive"))
      (node (ref "C176") (pin "2") (pinfunction "2_2") (pintype "passive"))
      (node (ref "C177") (pin "2") (pinfunction "2_2") (pintype "passive"))
      (node (ref "C178") (pin "1") (pinfunction "1_1") (pintype "passive"))
      (node (ref "C186") (pin "1") (pinfunction "1_1") (pintype "passive"))
      (node (ref "C187") (pin "2") (pinfunction "2_2") (pintype "passive"))
      (node (ref "C188") (pin "2") (pinfunction "2_2") (pintype "passive"))
      (node (ref "C189") (pin "2") (pinfunction "2_2") (pintype "passive"))
      (node (ref "C190") (pin "2") (pinfunction "2_2") (pintype "passive"))
      (node (ref "C191") (pin "2") (pinfunction "2_2") (pintype "passive"))
      (node (ref "C192") (pin "2") (pinfunction "2_2") (pintype "passive"))
      (node (ref "C193") (pin "1") (pinfunction "1_1") (pintype "passive"))
      (node (ref "C194") (pin "1") (pinfunction "1_1") (pintype "passive"))
      (node (ref "C195") (pin "2") (pinfunction "2_2") (pintype "passive"))
      (node (ref "C196") (pin "2") (pinfunction "2_2") (pintype "passive"))
      (node (ref "C197") (pin "2") (pinfunction "2_2") (pintype "passive"))
      (node (ref "C198") (pin "2") (pinfunction "2_2") (pintype "passive"))
      (node (ref "C199") (pin "2") (pinfunction "2_2") (pintype "passive"))
      (node (ref "C200") (pin "2") (pinfunction "2_2") (pintype "passive"))
      (node (ref "C201") (pin "1") (pinfunction "1_1") (pintype "passive"))
      (node (ref "R84") (pin "1") (pinfunction "1_1") (pintype "passive"))
      (node (ref "U18") (pin "A1") (pinfunction "VDDQ_A1") (pintype "power_in"))
      (node (ref "U18") (pin "A8") (pinfunction "VDDQ_A8") (pintype "power_in"))
      (node (ref "U18") (pin "B2") (pinfunction "VDD_B2") (pintype "power_in"))
      (node (ref "U18") (pin "C1") (pinfunction "VDDQ_C1") (pintype "power_in"))
      (node (ref "U18") (pin "C9") (pinfunction "VDDQ_C9") (pintype "power_in"))
      (node (ref "U18") (pin "D2") (pinfunction "VDDQ_D2") (pintype "power_in"))
      (node (ref "U18") (pin "D9") (pinfunction "VDD_D9") (pintype "power_in"))
      (node (ref "U18") (pin "E9") (pinfunction "VDDQ_E9") (pintype "power_in"))
      (node (ref "U18") (pin "F1") (pinfunction "VDDQ_F1") (pintype "power_in"))
      (node (ref "U18") (pin "G7") (pinfunction "VDD_G7") (pintype "power_in"))
      (node (ref "U18") (pin "H2") (pinfunction "VDDQ_H2") (pintype "power_in"))
      (node (ref "U18") (pin "H9") (pinfunction "VDDQ_H9") (pintype "power_in"))
      (node (ref "U18") (pin "K2") (pinfunction "VDD_K2") (pintype "power_in"))
      (node (ref "U18") (pin "K8") (pinfunction "VDD_K8") (pintype "power_in"))
      (node (ref "U18") (pin "N1") (pinfunction "VDD_N1") (pintype "power_in"))
      (node (ref "U18") (pin "N9") (pinfunction "VDD_N9") (pintype "power_in"))
      (node (ref "U18") (pin "R1") (pinfunction "VDD_R1") (pintype "power_in"))
      (node (ref "U18") (pin "R9") (pinfunction "VDD_R9") (pintype "power_in"))
      (node (ref "U19") (pin "2") (pinfunction "VLDOIN_2") (pintype "power_in"))
      (node (ref "U20") (pin "A1") (pinfunction "VDDQ_A1") (pintype "power_in"))
      (node (ref "U20") (pin "A8") (pinfunction "VDDQ_A8") (pintype "power_in"))
      (node (ref "U20") (pin "B2") (pinfunction "VDD_B2") (pintype "power_in"))
      (node (ref "U20") (pin "C1") (pinfunction "VDDQ_C1") (pintype "power_in"))
      (node (ref "U20") (pin "C9") (pinfunction "VDDQ_C9") (pintype "power_in"))
      (node (ref "U20") (pin "D2") (pinfunction "VDDQ_D2") (pintype "power_in"))
      (node (ref "U20") (pin "D9") (pinfunction "VDD_D9") (pintype "power_in"))
      (node (ref "U20") (pin "E9") (pinfunction "VDDQ_E9") (pintype "power_in"))
      (node (ref "U20") (pin "F1") (pinfunction "VDDQ_F1") (pintype "power_in"))
      (node (ref "U20") (pin "G7") (pinfunction "VDD_G7") (pintype "power_in"))
      (node (ref "U20") (pin "H2") (pinfunction "VDDQ_H2") (pintype "power_in"))
      (node (ref "U20") (pin "H9") (pinfunction "VDDQ_H9") (pintype "power_in"))
      (node (ref "U20") (pin "K2") (pinfunction "VDD_K2") (pintype "power_in"))
      (node (ref "U20") (pin "K8") (pinfunction "VDD_K8") (pintype "power_in"))
      (node (ref "U20") (pin "N1") (pinfunction "VDD_N1") (pintype "power_in"))
      (node (ref "U20") (pin "N9") (pinfunction "VDD_N9") (pintype "power_in"))
      (node (ref "U20") (pin "R1") (pinfunction "VDD_R1") (pintype "power_in"))
      (node (ref "U20") (pin "R9") (pinfunction "VDD_R9") (pintype "power_in"))
    )
    (net (code "74") (name "3V3") (class "Default")
      (node (ref "C148") (pin "1") (pinfunction "1_1") (pintype "passive"))
      (node (ref "R83") (pin "1") (pinfunction "1_1") (pintype "passive"))
      (node (ref "U19") (pin "10") (pinfunction "VIN_10") (pintype "power_in"))
      (node (ref "U19") (pin "7") (pinfunction "EN_7") (pintype "input"))
    )
    (net (code "75") (name "DDR_VTT") (class "Default")
      (node (ref "C149") (pin "1") (pinfunction "1_1") (pintype "passive"))
      (node (ref "C150") (pin "1") (pinfunction "1_1") (pintype "passive"))
      (node (ref "C151") (pin "2") (pinfunction "2_2") (pintype "passive"))
      (node (ref "C156") (pin "1") (pinfunction "1_1") (pintype "passive"))
      (node (ref "C157") (pin "1") (pinfunction "1_1") (pintype "passive"))
      (node (ref "C158") (pin "2") (pinfunction "2_2") (pintype "passive"))
      (node (ref "C159") (pin "2") (pinfunction "2_2") (pintype "passive"))
      (node (ref "C160") (pin "1") (pinfunction "1_1") (pintype "passive"))
      (node (ref "C161") (pin "1") (pinfunction "1_1") (pintype "passive"))
      (node (ref "C162") (pin "2") (pinfunction "2_2") (pintype "passive"))
      (node (ref "C179") (pin "1") (pinfunction "1_1") (pintype "passive"))
      (node (ref "C180") (pin "1") (pinfunction "1_1") (pintype "passive"))
      (node (ref "C181") (pin "1") (pinfunction "1_1") (pintype "passive"))
      (node (ref "C182") (pin "1") (pinfunction "1_1") (pintype "passive"))
      (node (ref "C183") (pin "1") (pinfunction "1_1") (pintype "passive"))
      (node (ref "C184") (pin "1") (pinfunction "1_1") (pintype "passive"))
      (node (ref "C185") (pin "2") (pinfunction "2_2") (pintype "passive"))
      (node (ref "R100") (pin "1") (pinfunction "1_1") (pintype "passive"))
      (node (ref "R101") (pin "1") (pinfunction "1_1") (pintype "passive"))
      (node (ref "R102") (pin "1") (pinfunction "1_1") (pintype "passive"))
      (node (ref "R103") (pin "1") (pinfunction "1_1") (pintype "passive"))
      (node (ref "R104") (pin "1") (pinfunction "1_1") (pintype "passive"))
      (node (ref "R105") (pin "1") (pinfunction "1_1") (pintype "passive"))
      (node (ref "R106") (pin "1") (pinfunction "1_1") (pintype "passive"))
      (node (ref "R107") (pin "1") (pinfunction "1_1") (pintype "passive"))
      (node (ref "R108") (pin "1") (pinfunction "1_1") (pintype "passive"))
      (node (ref "R109") (pin "1") (pinfunction "1_1") (pintype "passive"))
      (node (ref "R110") (pin "1") (pinfunction "1_1") (pintype "passive"))
      (node (ref "R88") (pin "1") (pinfunction "1_1") (pintype "passive"))
      (node (ref "R89") (pin "1") (pinfunction "1_1") (pintype "passive"))
      (node (ref "R90") (pin "1") (pinfunction "1_1") (pintype "passive"))
      (node (ref "R91") (pin "1") (pinfunction "1_1") (pintype "passive"))
      (node (ref "R92") (pin "1") (pinfunction "1_1") (pintype "passive"))
      (node (ref "R93") (pin "1") (pinfunction "1_1") (pintype "passive"))
      (node (ref "R94") (pin "1") (pinfunction "1_1") (pintype "passive"))
      (node (ref "R95") (pin "1") (pinfunction "1_1") (pintype "passive"))
      (node (ref "R96") (pin "1") (pinfunction "1_1") (pintype "passive"))
      (node (ref "R97") (pin "1") (pinfunction "1_1") (pintype "passive"))
      (node (ref "R98") (pin "1") (pinfunction "1_1") (pintype "passive"))
      (node (ref "R99") (pin "1") (pinfunction "1_1") (pintype "passive"))
      (node (ref "U18") (pin "H1") (pinfunction "VREFDQ_H1") (pintype "input"))
      (node (ref "U18") (pin "M8") (pinfunction "VREFCA_M8") (pintype "input"))
      (node (ref "U19") (pin "3") (pinfunction "VO_3") (pintype "power_in"))
      (node (ref "U20") (pin "H1") (pinfunction "VREFDQ_H1") (pintype "input"))
      (node (ref "U20") (pin "M8") (pinfunction "VREFCA_M8") (pintype "input"))
    )
    (net (code "76") (name "GND") (class "Default")
      (node (ref "C148") (pin "2") (pinfunction "2_2") (pintype "passive"))
      (node (ref "C149") (pin "2") (pinfunction "2_2") (pintype "passive"))
      (node (ref "C150") (pin "2") (pinfunction "2_2") (pintype "passive"))
      (node (ref "C151") (pin "1") (pinfunction "1_1") (pintype "passive"))
      (node (ref "C152") (pin "2") (pinfunction "2_2") (pintype "passive"))
      (node (ref "C153") (pin "1") (pinfunction "1_1") (pintype "passive"))
      (node (ref "C154") (pin "2") (pinfunction "2_2") (pintype "passive"))
      (node (ref "C155") (pin "2") (pinfunction "2_2") (pintype "passive"))
      (node (ref "C156") (pin "2") (pinfunction "2_2") (pintype "passive"))
      (node (ref "C157") (pin "2") (pinfunction "2_2") (pintype "passive"))
      (node (ref "C158") (pin "1") (pinfunction "1_1") (pintype "passive"))
      (node (ref "C159") (pin "1") (pinfunction "1_1") (pintype "passive"))
      (node (ref "C160") (pin "2") (pinfunction "2_2") (pintype "passive"))
      (node (ref "C161") (pin "2") (pinfunction "2_2") (pintype "passive"))
      (node (ref "C162") (pin "1") (pinfunction "1_1") (pintype "passive"))
      (node (ref "C163") (pin "2") (pinfunction "2_2") (pintype "passive"))
      (node (ref "C164") (pin "2") (pinfunction "2_2") (pintype "passive"))
      (node (ref "C165") (pin "2") (pinfunction "2_2") (pintype "passive"))
      (node (ref "C166") (pin "2") (pinfunction "2_2") (pintype "passive"))
      (node (ref "C167") (pin "2") (pinfunction "2_2") (pintype "passive"))
      (node (ref "C168") (pin "1") (pinfunction "1_1") (pintype "passive"))
      (node (ref "C169") (pin "2") (pinfunction "2_2") (pintype "passive"))
      (node (ref "C170") (pin "2") (pinfunction "2_2") (pintype "passive"))
      (node (ref "C171") (pin "2") (pinfunction "2_2") (pintype "passive"))
      (node (ref "C172") (pin "1") (pinfunction "1_1") (pintype "passive"))
      (node (ref "C173") (pin "1") (pinfunction "1_1") (pintype "passive"))
      (node (ref "C174") (pin "1") (pinfunction "1_1") (pintype "passive"))
      (node (ref "C175") (pin "1") (pinfunction "1_1") (pintype "passive"))
      (node (ref "C176") (pin "1") (pinfunction "1_1") (pintype "passive"))
      (node (ref "C177") (pin "1") (pinfunction "1_1") (pintype "passive"))
      (node (ref "C178") (pin "2") (pinfunction "2_2") (pintype "passive"))
      (node (ref "C179") (pin "2") (pinfunction "2_2") (pintype "passive"))
      (node (ref "C180") (pin "2") (pinfunction "2_2") (pintype "passive"))
      (node (ref "C181") (pin "2") (pinfunction "2_2") (pintype "passive"))
      (node (ref "C182") (pin "2") (pinfunction "2_2") (pintype "passive"))
      (node (ref "C183") (pin "2") (pinfunction "2_2") (pintype "passive"))
      (node (ref "C184") (pin "2") (pinfunction "2_2") (pintype "passive"))
      (node (ref "C185") (pin "1") (pinfunction "1_1") (pintype "passive"))
      (node (ref "C186") (pin "2") (pinfunction "2_2") (pintype "passive"))
      (node (ref "C187") (pin "1") (pinfunction "1_1") (pintype "passive"))
      (node (ref "C188") (pin "1") (pinfunction "1_1") (pintype "passive"))
      (node (ref "C189") (pin "1") (pinfunction "1_1") (pintype "passive"))
      (node (ref "C190") (pin "1") (pinfunction "1_1") (pintype "passive"))
      (node (ref "C191") (pin "1") (pinfunction "1_1") (pintype "passive"))
      (node (ref "C192") (pin "1") (pinfunction "1_1") (pintype "passive"))
      (node (ref "C193") (pin "2") (pinfunction "2_2") (pintype "passive"))
      (node (ref "C194") (pin "2") (pinfunction "2_2") (pintype "passive"))
      (node (ref "C195") (pin "1") (pinfunction "1_1") (pintype "passive"))
      (node (ref "C196") (pin "1") (pinfunction "1_1") (pintype "passive"))
      (node (ref "C197") (pin "1") (pinfunction "1_1") (pintype "passive"))
      (node (ref "C198") (pin "1") (pinfunction "1_1") (pintype "passive"))
      (node (ref "C199") (pin "1") (pinfunction "1_1") (pintype "passive"))
      (node (ref "C200") (pin "1") (pinfunction "1_1") (pintype "passive"))
      (node (ref "C201") (pin "2") (pinfunction "2_2") (pintype "passive"))
      (node (ref "R111") (pin "2") (pinfunction "2_2") (pintype "passive"))
      (node (ref "R112") (pin "1") (pinfunction "1_1") (pintype "passive"))
      (node (ref "R115") (pin "2") (pinfunction "2_2") (pintype "passive"))
      (node (ref "R85") (pin "2") (pinfunction "2_2") (pintype "passive"))
      (node (ref "R87") (pin "1") (pinfunction "1_1") (pintype "passive"))
      (node (ref "U18") (pin "A9") (pinfunction "VSS_A9") (pintype "power_in"))
      (node (ref "U18") (pin "B1") (pinfunction "VSSQ_B1") (pintype "power_in"))
      (node (ref "U18") (pin "B3") (pinfunction "VSS_B3") (pintype "power_in"))
      (node (ref "U18") (pin "B9") (pinfunction "VSSQ_B9") (pintype "power_in"))
      (node (ref "U18") (pin "D1") (pinfunction "VSSQ_D1") (pintype "power_in"))
      (node (ref "U18") (pin "D8") (pinfunction "VSSQ_D8") (pintype "power_in"))
      (node (ref "U18") (pin "E1") (pinfunction "VSS_E1") (pintype "power_in"))
      (node (ref "U18") (pin "E2") (pinfunction "VSSQ_E2") (pintype "power_in"))
      (node (ref "U18") (pin "E8") (pinfunction "VSSQ_E8") (pintype "power_in"))
      (node (ref "U18") (pin "F9") (pinfunction "VSSQ_F9") (pintype "power_in"))
      (node (ref "U18") (pin "G1") (pinfunction "VSSQ_G1") (pintype "power_in"))
      (node (ref "U18") (pin "G8") (pinfunction "VSS_G8") (pintype "power_in"))
      (node (ref "U18") (pin "G9") (pinfunction "VSSQ_G9") (pintype "power_in"))
      (node (ref "U18") (pin "J2") (pinfunction "VSS_J2") (pintype "power_in"))
      (node (ref "U18") (pin "J8") (pinfunction "VSS_J8") (pintype "power_in"))
      (node (ref "U18") (pin "M1") (pinfunction "VSS_M1") (pintype "power_in"))
      (node (ref "U18") (pin "M9") (pinfunction "VSS_M9") (pintype "power_in"))
      (node (ref "U18") (pin "P1") (pinfunction "VSS_P1") (pintype "power_in"))
      (node (ref "U18") (pin "P9") (pinfunction "VSS_P9") (pintype "power_in"))
      (node (ref "U18") (pin "T1") (pinfunction "VSS_T1") (pintype "power_in"))
      (node (ref "U18") (pin "T9") (pinfunction "VSS_T9") (pintype "power_in"))
      (node (ref "U19") (pin "11") (pinfunction "EP_11") (pintype "power_in"))
      (node (ref "U19") (pin "4") (pinfunction "PGND_4") (pintype "power_in"))
      (node (ref "U19") (pin "5") (pinfunction "VOSNS_5") (pintype "power_in"))
      (node (ref "U19") (pin "8") (pinfunction "GND_8") (pintype "power_in"))
      (node (ref "U20") (pin "A9") (pinfunction "VSS_A9") (pintype "power_in"))
      (node (ref "U20") (pin "B1") (pinfunction "VSSQ_B1") (pintype "power_in"))
      (node (ref "U20") (pin "B3") (pinfunction "VSS_B3") (pintype "power_in"))
      (node (ref "U20") (pin "B9") (pinfunction "VSSQ_B9") (pintype "power_in"))
      (node (ref "U20") (pin "D1") (pinfunction "VSSQ_D1") (pintype "power_in"))
      (node (ref "U20") (pin "D8") (pinfunction "VSSQ_D8") (pintype "power_in"))
      (node (ref "U20") (pin "E1") (pinfunction "VSS_E1") (pintype "power_in"))
      (node (ref "U20") (pin "E2") (pinfunction "VSSQ_E2") (pintype "power_in"))
      (node (ref "U20") (pin "E8") (pinfunction "VSSQ_E8") (pintype "power_in"))
      (node (ref "U20") (pin "F9") (pinfunction "VSSQ_F9") (pintype "power_in"))
      (node (ref "U20") (pin "G1") (pinfunction "VSSQ_G1") (pintype "power_in"))
      (node (ref "U20") (pin "G8") (pinfunction "VSS_G8") (pintype "power_in"))
      (node (ref "U20") (pin "G9") (pinfunction "VSSQ_G9") (pintype "power_in"))
      (node (ref "U20") (pin "J2") (pinfunction "VSS_J2") (pintype "power_in"))
      (node (ref "U20") (pin "J8") (pinfunction "VSS_J8") (pintype "power_in"))
      (node (ref "U20") (pin "M1") (pinfunction "VSS_M1") (pintype "power_in"))
      (node (ref "U20") (pin "M9") (pinfunction "VSS_M9") (pintype "power_in"))
      (node (ref "U20") (pin "P1") (pinfunction "VSS_P1") (pintype "power_in"))
      (node (ref "U20") (pin "P9") (pinfunction "VSS_P9") (pintype "power_in"))
      (node (ref "U20") (pin "T1") (pinfunction "VSS_T1") (pintype "power_in"))
      (node (ref "U20") (pin "T9") (pinfunction "VSS_T9") (pintype "power_in"))
    )
    (net (code "77") (name "Net-(U18A-ZQ)") (class "Default")
      (node (ref "R111") (pin "1") (pinfunction "1_1") (pintype "passive"))
      (node (ref "U18") (pin "L8") (pinfunction "ZQ_L8") (pintype "input"))
    )
    (net (code "78") (name "Net-(U19-PGOOD)") (class "Default")
      (node (ref "R83") (pin "2") (pinfunction "2_2") (pintype "passive"))
      (node (ref "U19") (pin "9") (pinfunction "PGOOD_9") (pintype "output"))
    )
    (net (code "79") (name "Net-(U19-REFIN)") (class "Default")
      (node (ref "C153") (pin "2") (pinfunction "2_2") (pintype "passive"))
      (node (ref "R84") (pin "2") (pinfunction "2_2") (pintype "passive"))
      (node (ref "R85") (pin "1") (pinfunction "1_1") (pintype "passive"))
      (node (ref "U19") (pin "1") (pinfunction "REFIN_1") (pintype "input"))
    )
    (net (code "80") (name "Net-(U20A-ZQ)") (class "Default")
      (node (ref "R115") (pin "1") (pinfunction "1_1") (pintype "passive"))
      (node (ref "U20") (pin "L8") (pinfunction "ZQ_L8") (pintype "input"))
    )
    (net (code "81") (name "VTT_REF") (class "Default")
      (node (ref "C152") (pin "1") (pinfunction "1_1") (pintype "passive"))
      (node (ref "U19") (pin "6") (pinfunction "REFOUT_6") (pintype "output"))
    )
    (net (code "82") (name "unconnected-(U18C-NC-PadJ1)") (class "Default")
      (node (ref "U18") (pin "J1") (pinfunction "NC_J1") (pintype "passive+no_connect"))
    )
    (net (code "83") (name "unconnected-(U18C-NC-PadJ9)") (class "Default")
      (node (ref "U18") (pin "J9") (pinfunction "NC_J9") (pintype "passive+no_connect"))
    )
    (net (code "84") (name "unconnected-(U18C-NC-PadL1)") (class "Default")
      (node (ref "U18") (pin "L1") (pinfunction "NC_L1") (pintype "passive+no_connect"))
    )
    (net (code "85") (name "unconnected-(U18C-NC-PadL9)") (class "Default")
      (node (ref "U18") (pin "L9") (pinfunction "NC_L9") (pintype "passive+no_connect"))
    )
    (net (code "86") (name "unconnected-(U20C-NC-PadJ1)") (class "Default")
      (node (ref "U20") (pin "J1") (pinfunction "NC_J1") (pintype "passive+no_connect"))
    )
    (net (code "87") (name "unconnected-(U20C-NC-PadJ9)") (class "Default")
      (node (ref "U20") (pin "J9") (pinfunction "NC_J9") (pintype "passive+no_connect"))
    )
    (net (code "88") (name "unconnected-(U20C-NC-PadL1)") (class "Default")
      (node (ref "U20") (pin "L1") (pinfunction "NC_L1") (pintype "passive+no_connect"))
    )
    (net (code "89") (name "unconnected-(U20C-NC-PadL9)") (class "Default")
      (node (ref "U20") (pin "L9") (pinfunction "NC_L9") (pintype "passive+no_connect"))
    )
  )
)
